# apollo_sensor_v4.net
KiCad netlist of a schematic drawn in EAGLE
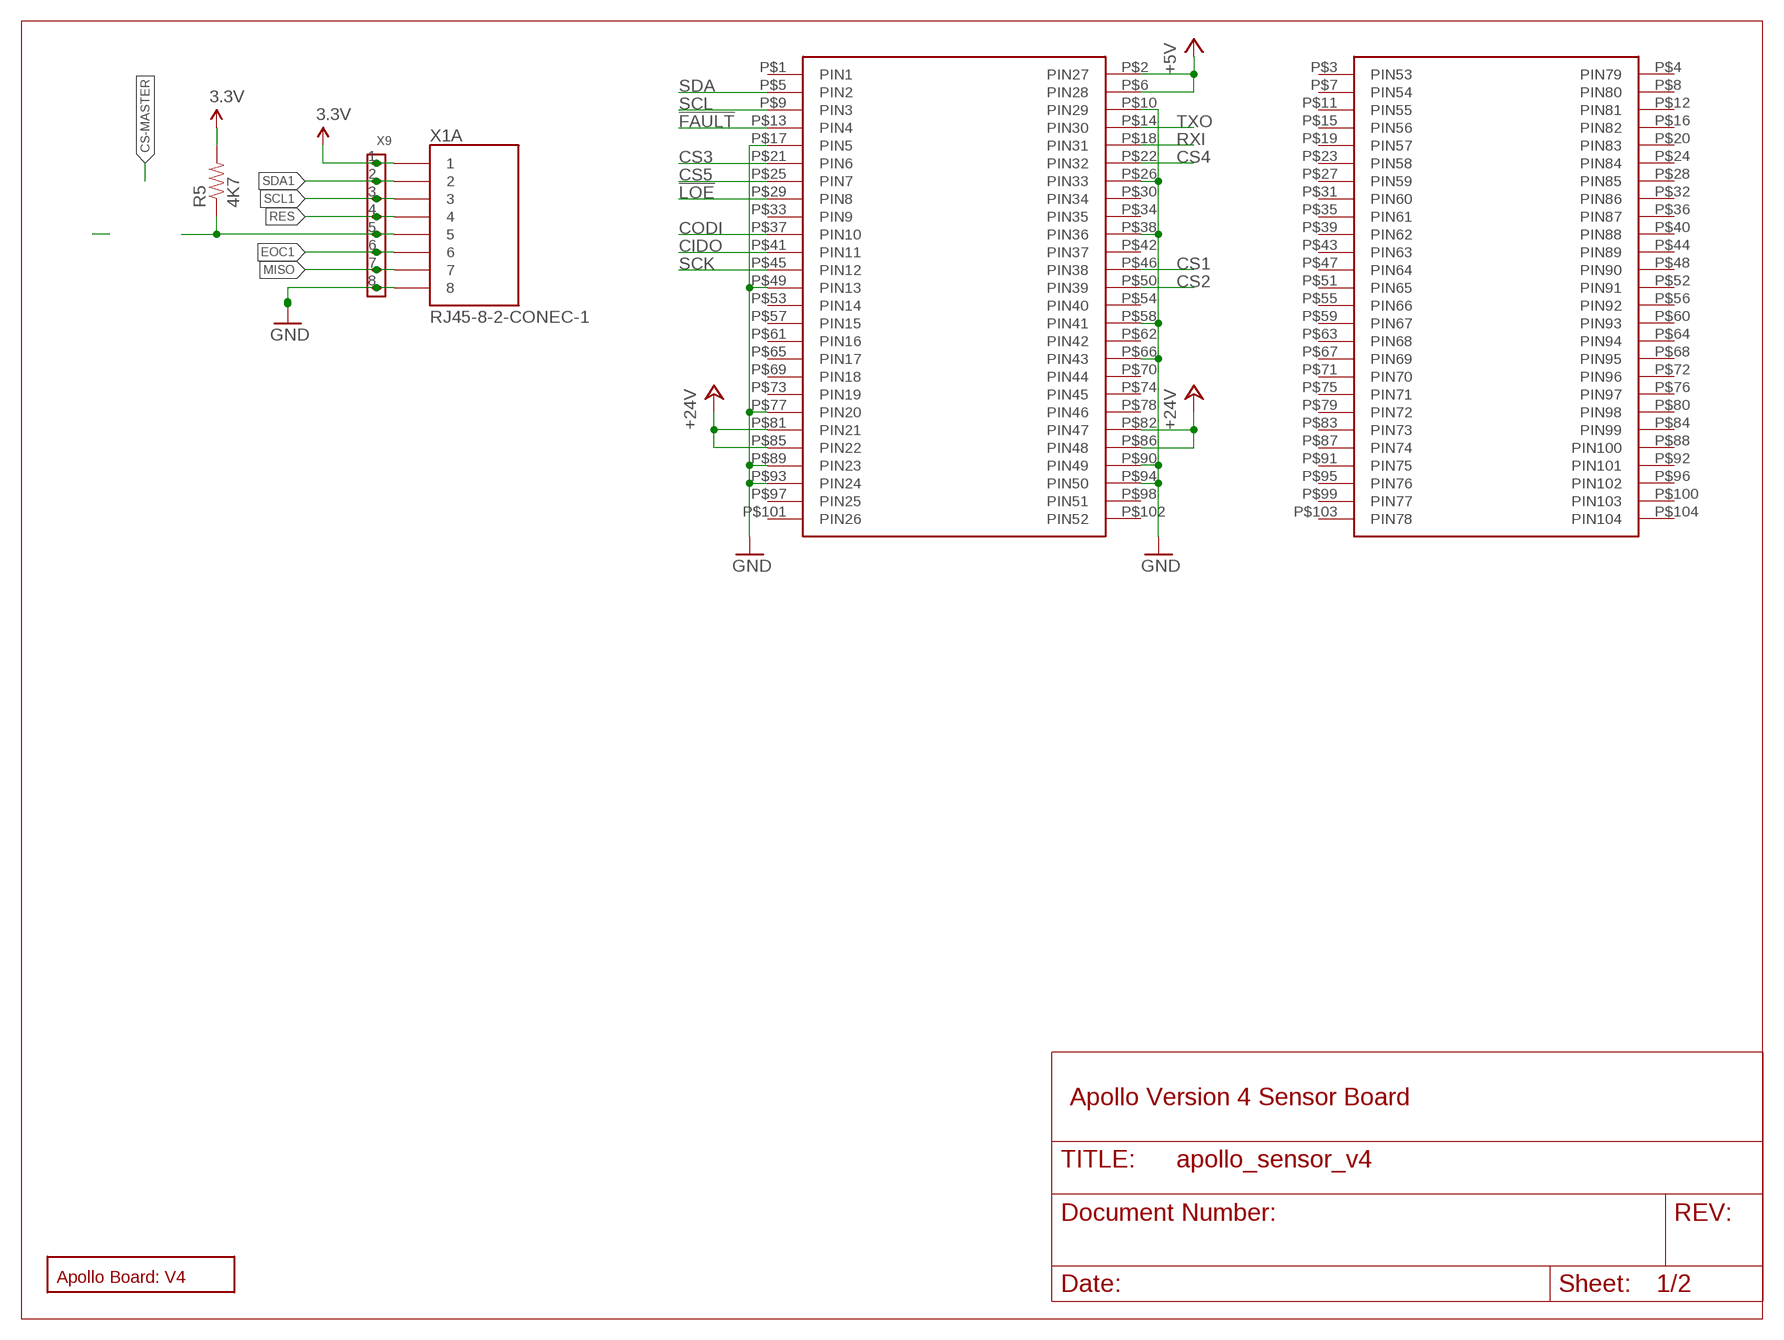
[diagram p0: schematic, sheet 1]

(export (version "E")
  (design (tool "Eeschema 10.0.6"))
  (components
    (comp (ref "R5")
      (value "4K7")
      (footprint "eagle-import:0805")
      (libsource (lib "eagle-import") (part "RESISTOR0805-RES"))
    )
    (comp (ref "U$1")
      (value "PC104_CONNECTOR")
      (footprint "eagle-import:PC104_CONNECTOR")
      (libsource (lib "eagle-import") (part "PC104_CONNECTOR"))
    )
    (comp (ref "U$2")
      (value "BOARD_TEMPLATE1")
      (footprint "eagle-import:BOARD_TEMPLATE")
      (libsource (lib "eagle-import") (part "BOARD_TEMPLATE1"))
    )
    (comp (ref "X1")
      (value "RJ45-8-2-CONEC-1")
      (footprint "eagle-import:CONEC-33TS3004ST-88001")
      (libsource (lib "eagle-import") (part "RJ45-8-2-CONEC-1"))
    )
    (comp (ref "X9")
      (value "TP-GROUP-X8-2X04")
      (footprint "eagle-import:2X4")
      (libsource (lib "eagle-import") (part "TP-GROUP-X8-2X04"))
    )
  )
  (nets
    (net (code "1") (name "+5V") (class "Default")
      (node (ref "U$1") (pin "P$2") (pinfunction "PIN27_P$2") (pintype "bidirectional"))
      (node (ref "U$1") (pin "P$6") (pinfunction "PIN28_P$6") (pintype "bidirectional"))
    )
    (net (code "2") (name "+24V") (class "Default")
      (node (ref "U$1") (pin "P$81") (pinfunction "PIN21_P$81") (pintype "bidirectional"))
      (node (ref "U$1") (pin "P$82") (pinfunction "PIN47_P$82") (pintype "bidirectional"))
      (node (ref "U$1") (pin "P$85") (pinfunction "PIN22_P$85") (pintype "bidirectional"))
      (node (ref "U$1") (pin "P$86") (pinfunction "PIN48_P$86") (pintype "bidirectional"))
    )
    (net (code "3") (name "3.3V") (class "Default")
      (node (ref "R5") (pin "2") (pinfunction "2_2") (pintype "passive"))
      (node (ref "X1") (pin "1") (pinfunction "1_1") (pintype "bidirectional"))
      (node (ref "X9") (pin "1") (pinfunction "P$1_1") (pintype "bidirectional"))
    )
    (net (code "4") (name "CIDO") (class "Default")
      (node (ref "U$1") (pin "P$41") (pinfunction "PIN11_P$41") (pintype "bidirectional"))
    )
    (net (code "5") (name "CODI") (class "Default")
      (node (ref "U$1") (pin "P$37") (pinfunction "PIN10_P$37") (pintype "bidirectional"))
    )
    (net (code "7") (name "CS1") (class "Default")
      (node (ref "U$1") (pin "P$46") (pinfunction "PIN38_P$46") (pintype "bidirectional"))
    )
    (net (code "8") (name "CS2") (class "Default")
      (node (ref "U$1") (pin "P$50") (pinfunction "PIN39_P$50") (pintype "bidirectional"))
    )
    (net (code "9") (name "CS3") (class "Default")
      (node (ref "U$1") (pin "P$21") (pinfunction "PIN6_P$21") (pintype "bidirectional"))
    )
    (net (code "10") (name "CS4") (class "Default")
      (node (ref "U$1") (pin "P$22") (pinfunction "PIN32_P$22") (pintype "bidirectional"))
    )
    (net (code "11") (name "CS5") (class "Default")
      (node (ref "U$1") (pin "P$25") (pinfunction "PIN7_P$25") (pintype "bidirectional"))
    )
    (net (code "12") (name "EOC1") (class "Default")
      (node (ref "X1") (pin "6") (pinfunction "6_6") (pintype "bidirectional"))
      (node (ref "X9") (pin "6") (pinfunction "P$6_6") (pintype "bidirectional"))
    )
    (net (code "13") (name "GND") (class "Default")
      (node (ref "U$1") (pin "P$10") (pinfunction "PIN29_P$10") (pintype "bidirectional"))
      (node (ref "U$1") (pin "P$17") (pinfunction "PIN5_P$17") (pintype "bidirectional"))
      (node (ref "U$1") (pin "P$26") (pinfunction "PIN33_P$26") (pintype "bidirectional"))
      (node (ref "U$1") (pin "P$38") (pinfunction "PIN36_P$38") (pintype "bidirectional"))
      (node (ref "U$1") (pin "P$49") (pinfunction "PIN13_P$49") (pintype "bidirectional"))
      (node (ref "U$1") (pin "P$58") (pinfunction "PIN41_P$58") (pintype "bidirectional"))
      (node (ref "U$1") (pin "P$66") (pinfunction "PIN43_P$66") (pintype "bidirectional"))
      (node (ref "U$1") (pin "P$77") (pinfunction "PIN20_P$77") (pintype "bidirectional"))
      (node (ref "U$1") (pin "P$89") (pinfunction "PIN23_P$89") (pintype "bidirectional"))
      (node (ref "U$1") (pin "P$90") (pinfunction "PIN49_P$90") (pintype "bidirectional"))
      (node (ref "U$1") (pin "P$93") (pinfunction "PIN24_P$93") (pintype "bidirectional"))
      (node (ref "U$1") (pin "P$94") (pinfunction "PIN50_P$94") (pintype "bidirectional"))
      (node (ref "X1") (pin "8") (pinfunction "8_8") (pintype "bidirectional"))
      (node (ref "X1") (pin "M1") (pinfunction "P$1_M1") (pintype "bidirectional"))
      (node (ref "X1") (pin "M2") (pinfunction "P$1_M2") (pintype "bidirectional"))
      (node (ref "X9") (pin "8") (pinfunction "P$8_8") (pintype "bidirectional"))
    )
    (net (code "14") (name "MISO") (class "Default")
      (node (ref "X1") (pin "7") (pinfunction "7_7") (pintype "bidirectional"))
      (node (ref "X9") (pin "7") (pinfunction "P$7_7") (pintype "bidirectional"))
    )
    (net (code "15") (name "Net-(X9-P$5)") (class "Default")
      (node (ref "R5") (pin "1") (pinfunction "1_1") (pintype "passive"))
      (node (ref "X1") (pin "5") (pinfunction "5_5") (pintype "bidirectional"))
      (node (ref "X9") (pin "5") (pinfunction "P$5_5") (pintype "bidirectional"))
    )
    (net (code "16") (name "RES") (class "Default")
      (node (ref "X1") (pin "4") (pinfunction "4_4") (pintype "bidirectional"))
      (node (ref "X9") (pin "4") (pinfunction "P$4_4") (pintype "bidirectional"))
    )
    (net (code "17") (name "RXI") (class "Default")
      (node (ref "U$1") (pin "P$18") (pinfunction "PIN31_P$18") (pintype "bidirectional"))
    )
    (net (code "18") (name "SCK") (class "Default")
      (node (ref "U$1") (pin "P$45") (pinfunction "PIN12_P$45") (pintype "bidirectional"))
    )
    (net (code "19") (name "SCL") (class "Default")
      (node (ref "U$1") (pin "P$9") (pinfunction "PIN3_P$9") (pintype "bidirectional"))
    )
    (net (code "20") (name "SCL1") (class "Default")
      (node (ref "X1") (pin "3") (pinfunction "3_3") (pintype "bidirectional"))
      (node (ref "X9") (pin "3") (pinfunction "P$3_3") (pintype "bidirectional"))
    )
    (net (code "21") (name "SDA") (class "Default")
      (node (ref "U$1") (pin "P$5") (pinfunction "PIN2_P$5") (pintype "bidirectional"))
    )
    (net (code "22") (name "SDA1") (class "Default")
      (node (ref "X1") (pin "2") (pinfunction "2_2") (pintype "bidirectional"))
      (node (ref "X9") (pin "2") (pinfunction "P$2_2") (pintype "bidirectional"))
    )
    (net (code "23") (name "TXO") (class "Default")
      (node (ref "U$1") (pin "P$14") (pinfunction "PIN30_P$14") (pintype "bidirectional"))
    )
    (net (code "24") (name "unconnected-(U$1-PIN1-PadP$1)") (class "Default")
      (node (ref "U$1") (pin "P$1") (pinfunction "PIN1_P$1") (pintype "bidirectional"))
    )
    (net (code "25") (name "unconnected-(U$1-PIN9-PadP$33)") (class "Default")
      (node (ref "U$1") (pin "P$33") (pinfunction "PIN9_P$33") (pintype "bidirectional"))
    )
    (net (code "26") (name "unconnected-(U$1-PIN14-PadP$53)") (class "Default")
      (node (ref "U$1") (pin "P$53") (pinfunction "PIN14_P$53") (pintype "bidirectional"))
    )
    (net (code "27") (name "unconnected-(U$1-PIN15-PadP$57)") (class "Default")
      (node (ref "U$1") (pin "P$57") (pinfunction "PIN15_P$57") (pintype "bidirectional"))
    )
    (net (code "28") (name "unconnected-(U$1-PIN16-PadP$61)") (class "Default")
      (node (ref "U$1") (pin "P$61") (pinfunction "PIN16_P$61") (pintype "bidirectional"))
    )
    (net (code "29") (name "unconnected-(U$1-PIN17-PadP$65)") (class "Default")
      (node (ref "U$1") (pin "P$65") (pinfunction "PIN17_P$65") (pintype "bidirectional"))
    )
    (net (code "30") (name "unconnected-(U$1-PIN18-PadP$69)") (class "Default")
      (node (ref "U$1") (pin "P$69") (pinfunction "PIN18_P$69") (pintype "bidirectional"))
    )
    (net (code "31") (name "unconnected-(U$1-PIN19-PadP$73)") (class "Default")
      (node (ref "U$1") (pin "P$73") (pinfunction "PIN19_P$73") (pintype "bidirectional"))
    )
    (net (code "32") (name "unconnected-(U$1-PIN25-PadP$97)") (class "Default")
      (node (ref "U$1") (pin "P$97") (pinfunction "PIN25_P$97") (pintype "bidirectional"))
    )
    (net (code "33") (name "unconnected-(U$1-PIN26-PadP$101)") (class "Default")
      (node (ref "U$1") (pin "P$101") (pinfunction "PIN26_P$101") (pintype "bidirectional"))
    )
    (net (code "34") (name "unconnected-(U$1-PIN34-PadP$30)") (class "Default")
      (node (ref "U$1") (pin "P$30") (pinfunction "PIN34_P$30") (pintype "bidirectional"))
    )
    (net (code "35") (name "unconnected-(U$1-PIN35-PadP$34)") (class "Default")
      (node (ref "U$1") (pin "P$34") (pinfunction "PIN35_P$34") (pintype "bidirectional"))
    )
    (net (code "36") (name "unconnected-(U$1-PIN37-PadP$42)") (class "Default")
      (node (ref "U$1") (pin "P$42") (pinfunction "PIN37_P$42") (pintype "bidirectional"))
    )
    (net (code "37") (name "unconnected-(U$1-PIN40-PadP$54)") (class "Default")
      (node (ref "U$1") (pin "P$54") (pinfunction "PIN40_P$54") (pintype "bidirectional"))
    )
    (net (code "38") (name "unconnected-(U$1-PIN42-PadP$62)") (class "Default")
      (node (ref "U$1") (pin "P$62") (pinfunction "PIN42_P$62") (pintype "bidirectional"))
    )
    (net (code "39") (name "unconnected-(U$1-PIN44-PadP$70)") (class "Default")
      (node (ref "U$1") (pin "P$70") (pinfunction "PIN44_P$70") (pintype "bidirectional"))
    )
    (net (code "40") (name "unconnected-(U$1-PIN45-PadP$74)") (class "Default")
      (node (ref "U$1") (pin "P$74") (pinfunction "PIN45_P$74") (pintype "bidirectional"))
    )
    (net (code "41") (name "unconnected-(U$1-PIN46-PadP$78)") (class "Default")
      (node (ref "U$1") (pin "P$78") (pinfunction "PIN46_P$78") (pintype "bidirectional"))
    )
    (net (code "42") (name "unconnected-(U$1-PIN51-PadP$98)") (class "Default")
      (node (ref "U$1") (pin "P$98") (pinfunction "PIN51_P$98") (pintype "bidirectional"))
    )
    (net (code "43") (name "unconnected-(U$1-PIN52-PadP$102)") (class "Default")
      (node (ref "U$1") (pin "P$102") (pinfunction "PIN52_P$102") (pintype "bidirectional"))
    )
    (net (code "44") (name "unconnected-(U$1-PIN53-PadP$3)") (class "Default")
      (node (ref "U$1") (pin "P$3") (pinfunction "PIN53_P$3") (pintype "bidirectional"))
    )
    (net (code "45") (name "unconnected-(U$1-PIN54-PadP$7)") (class "Default")
      (node (ref "U$1") (pin "P$7") (pinfunction "PIN54_P$7") (pintype "bidirectional"))
    )
    (net (code "46") (name "unconnected-(U$1-PIN55-PadP$11)") (class "Default")
      (node (ref "U$1") (pin "P$11") (pinfunction "PIN55_P$11") (pintype "bidirectional"))
    )
    (net (code "47") (name "unconnected-(U$1-PIN56-PadP$15)") (class "Default")
      (node (ref "U$1") (pin "P$15") (pinfunction "PIN56_P$15") (pintype "bidirectional"))
    )
    (net (code "48") (name "unconnected-(U$1-PIN57-PadP$19)") (class "Default")
      (node (ref "U$1") (pin "P$19") (pinfunction "PIN57_P$19") (pintype "bidirectional"))
    )
    (net (code "49") (name "unconnected-(U$1-PIN58-PadP$23)") (class "Default")
      (node (ref "U$1") (pin "P$23") (pinfunction "PIN58_P$23") (pintype "bidirectional"))
    )
    (net (code "50") (name "unconnected-(U$1-PIN59-PadP$27)") (class "Default")
      (node (ref "U$1") (pin "P$27") (pinfunction "PIN59_P$27") (pintype "bidirectional"))
    )
    (net (code "51") (name "unconnected-(U$1-PIN60-PadP$31)") (class "Default")
      (node (ref "U$1") (pin "P$31") (pinfunction "PIN60_P$31") (pintype "bidirectional"))
    )
    (net (code "52") (name "unconnected-(U$1-PIN61-PadP$35)") (class "Default")
      (node (ref "U$1") (pin "P$35") (pinfunction "PIN61_P$35") (pintype "bidirectional"))
    )
    (net (code "53") (name "unconnected-(U$1-PIN62-PadP$39)") (class "Default")
      (node (ref "U$1") (pin "P$39") (pinfunction "PIN62_P$39") (pintype "bidirectional"))
    )
    (net (code "54") (name "unconnected-(U$1-PIN63-PadP$43)") (class "Default")
      (node (ref "U$1") (pin "P$43") (pinfunction "PIN63_P$43") (pintype "bidirectional"))
    )
    (net (code "55") (name "unconnected-(U$1-PIN64-PadP$47)") (class "Default")
      (node (ref "U$1") (pin "P$47") (pinfunction "PIN64_P$47") (pintype "bidirectional"))
    )
    (net (code "56") (name "unconnected-(U$1-PIN65-PadP$51)") (class "Default")
      (node (ref "U$1") (pin "P$51") (pinfunction "PIN65_P$51") (pintype "bidirectional"))
    )
    (net (code "57") (name "unconnected-(U$1-PIN66-PadP$55)") (class "Default")
      (node (ref "U$1") (pin "P$55") (pinfunction "PIN66_P$55") (pintype "bidirectional"))
    )
    (net (code "58") (name "unconnected-(U$1-PIN67-PadP$59)") (class "Default")
      (node (ref "U$1") (pin "P$59") (pinfunction "PIN67_P$59") (pintype "bidirectional"))
    )
    (net (code "59") (name "unconnected-(U$1-PIN68-PadP$63)") (class "Default")
      (node (ref "U$1") (pin "P$63") (pinfunction "PIN68_P$63") (pintype "bidirectional"))
    )
    (net (code "60") (name "unconnected-(U$1-PIN69-PadP$67)") (class "Default")
      (node (ref "U$1") (pin "P$67") (pinfunction "PIN69_P$67") (pintype "bidirectional"))
    )
    (net (code "61") (name "unconnected-(U$1-PIN70-PadP$71)") (class "Default")
      (node (ref "U$1") (pin "P$71") (pinfunction "PIN70_P$71") (pintype "bidirectional"))
    )
    (net (code "62") (name "unconnected-(U$1-PIN71-PadP$75)") (class "Default")
      (node (ref "U$1") (pin "P$75") (pinfunction "PIN71_P$75") (pintype "bidirectional"))
    )
    (net (code "63") (name "unconnected-(U$1-PIN72-PadP$79)") (class "Default")
      (node (ref "U$1") (pin "P$79") (pinfunction "PIN72_P$79") (pintype "bidirectional"))
    )
    (net (code "64") (name "unconnected-(U$1-PIN73-PadP$83)") (class "Default")
      (node (ref "U$1") (pin "P$83") (pinfunction "PIN73_P$83") (pintype "bidirectional"))
    )
    (net (code "65") (name "unconnected-(U$1-PIN74-PadP$87)") (class "Default")
      (node (ref "U$1") (pin "P$87") (pinfunction "PIN74_P$87") (pintype "bidirectional"))
    )
    (net (code "66") (name "unconnected-(U$1-PIN75-PadP$91)") (class "Default")
      (node (ref "U$1") (pin "P$91") (pinfunction "PIN75_P$91") (pintype "bidirectional"))
    )
    (net (code "67") (name "unconnected-(U$1-PIN76-PadP$95)") (class "Default")
      (node (ref "U$1") (pin "P$95") (pinfunction "PIN76_P$95") (pintype "bidirectional"))
    )
    (net (code "68") (name "unconnected-(U$1-PIN77-PadP$99)") (class "Default")
      (node (ref "U$1") (pin "P$99") (pinfunction "PIN77_P$99") (pintype "bidirectional"))
    )
    (net (code "69") (name "unconnected-(U$1-PIN78-PadP$103)") (class "Default")
      (node (ref "U$1") (pin "P$103") (pinfunction "PIN78_P$103") (pintype "bidirectional"))
    )
    (net (code "70") (name "unconnected-(U$1-PIN79-PadP$4)") (class "Default")
      (node (ref "U$1") (pin "P$4") (pinfunction "PIN79_P$4") (pintype "bidirectional"))
    )
    (net (code "71") (name "unconnected-(U$1-PIN80-PadP$8)") (class "Default")
      (node (ref "U$1") (pin "P$8") (pinfunction "PIN80_P$8") (pintype "bidirectional"))
    )
    (net (code "72") (name "unconnected-(U$1-PIN81-PadP$12)") (class "Default")
      (node (ref "U$1") (pin "P$12") (pinfunction "PIN81_P$12") (pintype "bidirectional"))
    )
    (net (code "73") (name "unconnected-(U$1-PIN82-PadP$16)") (class "Default")
      (node (ref "U$1") (pin "P$16") (pinfunction "PIN82_P$16") (pintype "bidirectional"))
    )
    (net (code "74") (name "unconnected-(U$1-PIN83-PadP$20)") (class "Default")
      (node (ref "U$1") (pin "P$20") (pinfunction "PIN83_P$20") (pintype "bidirectional"))
    )
    (net (code "75") (name "unconnected-(U$1-PIN84-PadP$24)") (class "Default")
      (node (ref "U$1") (pin "P$24") (pinfunction "PIN84_P$24") (pintype "bidirectional"))
    )
    (net (code "76") (name "unconnected-(U$1-PIN85-PadP$28)") (class "Default")
      (node (ref "U$1") (pin "P$28") (pinfunction "PIN85_P$28") (pintype "bidirectional"))
    )
    (net (code "77") (name "unconnected-(U$1-PIN86-PadP$32)") (class "Default")
      (node (ref "U$1") (pin "P$32") (pinfunction "PIN86_P$32") (pintype "bidirectional"))
    )
    (net (code "78") (name "unconnected-(U$1-PIN87-PadP$36)") (class "Default")
      (node (ref "U$1") (pin "P$36") (pinfunction "PIN87_P$36") (pintype "bidirectional"))
    )
    (net (code "79") (name "unconnected-(U$1-PIN88-PadP$40)") (class "Default")
      (node (ref "U$1") (pin "P$40") (pinfunction "PIN88_P$40") (pintype "bidirectional"))
    )
    (net (code "80") (name "unconnected-(U$1-PIN89-PadP$44)") (class "Default")
      (node (ref "U$1") (pin "P$44") (pinfunction "PIN89_P$44") (pintype "bidirectional"))
    )
    (net (code "81") (name "unconnected-(U$1-PIN90-PadP$48)") (class "Default")
      (node (ref "U$1") (pin "P$48") (pinfunction "PIN90_P$48") (pintype "bidirectional"))
    )
    (net (code "82") (name "unconnected-(U$1-PIN91-PadP$52)") (class "Default")
      (node (ref "U$1") (pin "P$52") (pinfunction "PIN91_P$52") (pintype "bidirectional"))
    )
    (net (code "83") (name "unconnected-(U$1-PIN92-PadP$56)") (class "Default")
      (node (ref "U$1") (pin "P$56") (pinfunction "PIN92_P$56") (pintype "bidirectional"))
    )
    (net (code "84") (name "unconnected-(U$1-PIN93-PadP$60)") (class "Default")
      (node (ref "U$1") (pin "P$60") (pinfunction "PIN93_P$60") (pintype "bidirectional"))
    )
    (net (code "85") (name "unconnected-(U$1-PIN94-PadP$64)") (class "Default")
      (node (ref "U$1") (pin "P$64") (pinfunction "PIN94_P$64") (pintype "bidirectional"))
    )
    (net (code "86") (name "unconnected-(U$1-PIN95-PadP$68)") (class "Default")
      (node (ref "U$1") (pin "P$68") (pinfunction "PIN95_P$68") (pintype "bidirectional"))
    )
    (net (code "87") (name "unconnected-(U$1-PIN96-PadP$72)") (class "Default")
      (node (ref "U$1") (pin "P$72") (pinfunction "PIN96_P$72") (pintype "bidirectional"))
    )
    (net (code "88") (name "unconnected-(U$1-PIN97-PadP$76)") (class "Default")
      (node (ref "U$1") (pin "P$76") (pinfunction "PIN97_P$76") (pintype "bidirectional"))
    )
    (net (code "89") (name "unconnected-(U$1-PIN98-PadP$80)") (class "Default")
      (node (ref "U$1") (pin "P$80") (pinfunction "PIN98_P$80") (pintype "bidirectional"))
    )
    (net (code "90") (name "unconnected-(U$1-PIN99-PadP$84)") (class "Default")
      (node (ref "U$1") (pin "P$84") (pinfunction "PIN99_P$84") (pintype "bidirectional"))
    )
    (net (code "91") (name "unconnected-(U$1-PIN100-PadP$88)") (class "Default")
      (node (ref "U$1") (pin "P$88") (pinfunction "PIN100_P$88") (pintype "bidirectional"))
    )
    (net (code "92") (name "unconnected-(U$1-PIN101-PadP$92)") (class "Default")
      (node (ref "U$1") (pin "P$92") (pinfunction "PIN101_P$92") (pintype "bidirectional"))
    )
    (net (code "93") (name "unconnected-(U$1-PIN102-PadP$96)") (class "Default")
      (node (ref "U$1") (pin "P$96") (pinfunction "PIN102_P$96") (pintype "bidirectional"))
    )
    (net (code "94") (name "unconnected-(U$1-PIN103-PadP$100)") (class "Default")
      (node (ref "U$1") (pin "P$100") (pinfunction "PIN103_P$100") (pintype "bidirectional"))
    )
    (net (code "95") (name "unconnected-(U$1-PIN104-PadP$104)") (class "Default")
      (node (ref "U$1") (pin "P$104") (pinfunction "PIN104_P$104") (pintype "bidirectional"))
    )
    (net (code "96") (name "~{FAULT}") (class "Default")
      (node (ref "U$1") (pin "P$13") (pinfunction "PIN4_P$13") (pintype "bidirectional"))
    )
    (net (code "97") (name "~{LOE}") (class "Default")
      (node (ref "U$1") (pin "P$29") (pinfunction "PIN8_P$29") (pintype "bidirectional"))
    )
  )
)
